# DP_PS.net
KiCad netlist of a schematic drawn in Altium Designer
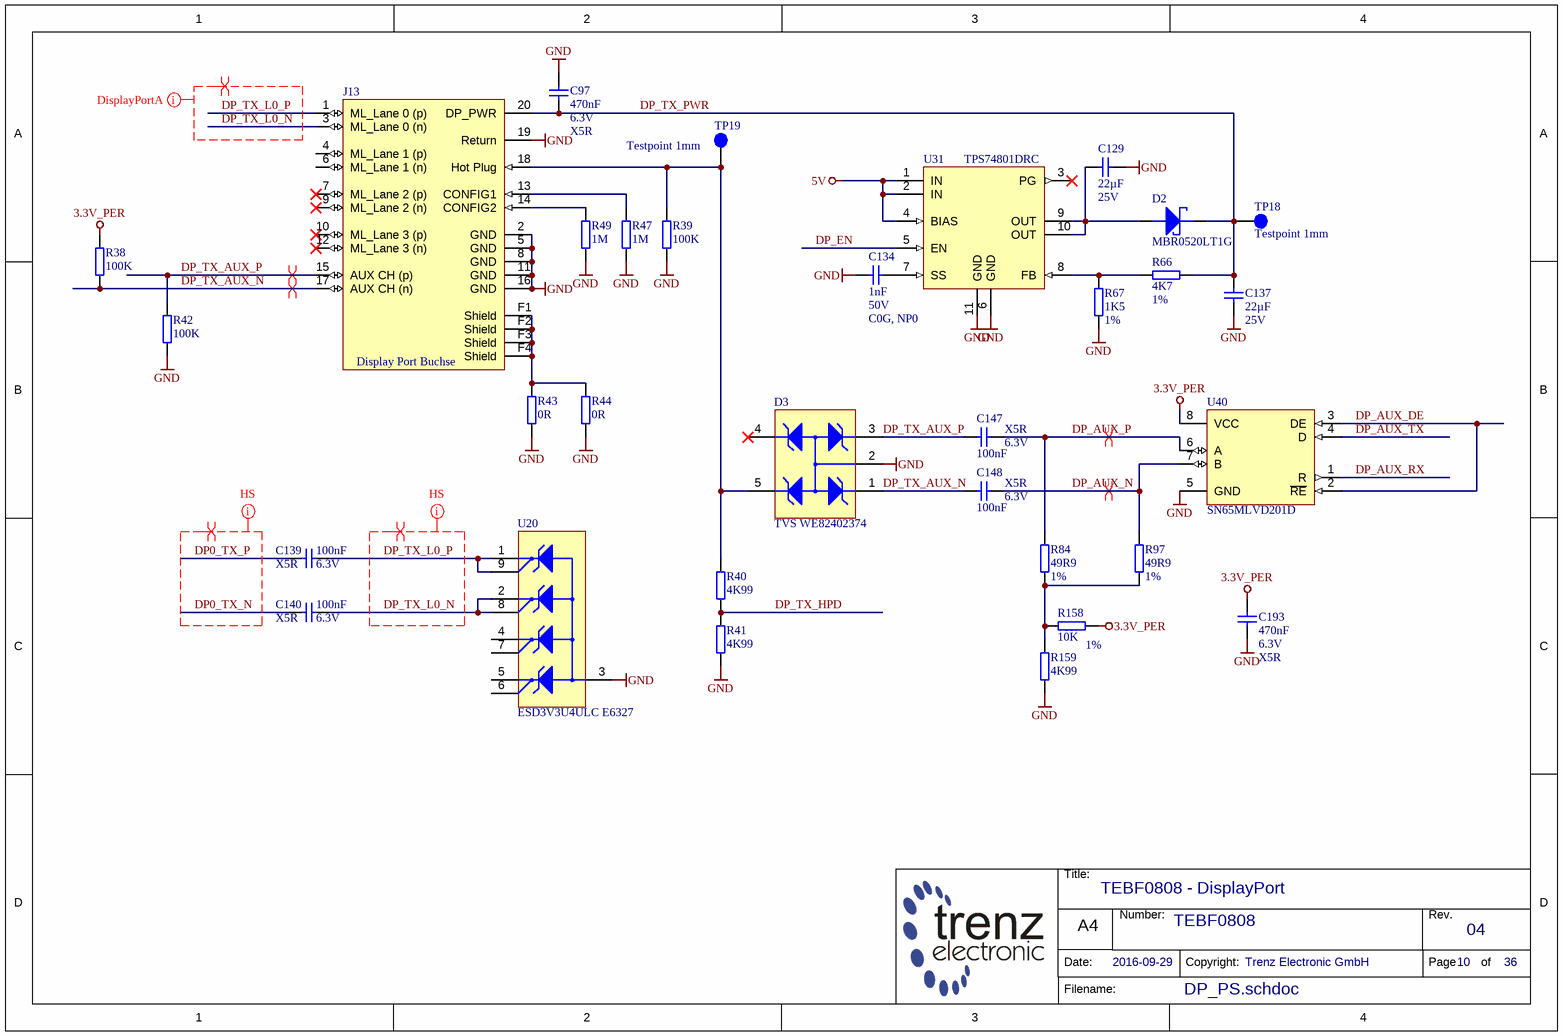
[diagram p0: DP_PS.schdoc]

(export (version "E")
  (design (tool "Eeschema 10.0.6"))
  (components
    (comp (ref "C97")
      (value "470nF")
      (footprint "CAPC1005X55N")
      (description "KON 470nF 6,3V X5R SMD")
      (fields (field (name "VOLTAGE") "6.3V") (field (name "TECHNOLOGY") "X5R"))
      (libsource (lib "TE") (part "CAP-NP"))
    )
    (comp (ref "C129")
      (value "22µF")
      (footprint "CAPC3216X180N")
      (description "KON 22µF X5R 25V SMD 10%")
      (fields (field (name "VOLTAGE") "25V") (field (name "TOLERANCE") "10%"))
      (libsource (lib "TE") (part "CAP-NP"))
    )
    (comp (ref "C134")
      (value "1nF")
      (footprint "CAPC1005X55N")
      (description "KON 1nF NP0 SMD 5%")
      (fields
        (field (name "VOLTAGE") "50V")
        (field (name "TECHNOLOGY") "C0G, NP0")
        (field (name "TOLERANCE") "5%")
      )
      (libsource (lib "TE") (part "CAP-NP"))
    )
    (comp (ref "C137")
      (value "22µF")
      (footprint "CAPC3216X180N")
      (description "KON 22µF X5R 25V SMD 10%")
      (fields (field (name "VOLTAGE") "25V") (field (name "TOLERANCE") "10%"))
      (libsource (lib "TE") (part "CAP-NP"))
    )
    (comp (ref "C139")
      (value "100nF")
      (footprint "CAPC0603X33N")
      (description "KON 100nF 6.3V X5R SMD 10%")
      (fields
        (field (name "VOLTAGE") "6.3V")
        (field (name "TECHNOLOGY") "X5R")
        (field (name "TOLERANCE") "10%")
      )
      (libsource (lib "TE") (part "CAP-NP"))
    )
    (comp (ref "C140")
      (value "100nF")
      (footprint "CAPC0603X33N")
      (description "KON 100nF 6.3V X5R SMD 10%")
      (fields
        (field (name "VOLTAGE") "6.3V")
        (field (name "TECHNOLOGY") "X5R")
        (field (name "TOLERANCE") "10%")
      )
      (libsource (lib "TE") (part "CAP-NP"))
    )
    (comp (ref "C147")
      (value "100nF")
      (footprint "CAPC0603X33N")
      (description "KON 100nF 6.3V X5R SMD 10%")
      (fields
        (field (name "VOLTAGE") "6.3V")
        (field (name "TECHNOLOGY") "X5R")
        (field (name "TOLERANCE") "10%")
      )
      (libsource (lib "TE") (part "CAP-NP"))
    )
    (comp (ref "C148")
      (value "100nF")
      (footprint "CAPC0603X33N")
      (description "KON 100nF 6.3V X5R SMD 10%")
      (fields
        (field (name "VOLTAGE") "6.3V")
        (field (name "TECHNOLOGY") "X5R")
        (field (name "TOLERANCE") "10%")
      )
      (libsource (lib "TE") (part "CAP-NP"))
    )
    (comp (ref "C193")
      (value "470nF")
      (footprint "CAPC1005X55N")
      (description "KON 470nF 6,3V X5R SMD")
      (fields (field (name "VOLTAGE") "6.3V") (field (name "TECHNOLOGY") "X5R"))
      (libsource (lib "TE") (part "CAP-NP"))
    )
    (comp (ref "D2")
      (value "MBR0520LT1G")
      (footprint "SOD3816X120N")
      (fields (field (name "VOLTAGE") "0.5A"))
      (libsource (lib "TE") (part "SCHOTTKY"))
    )
    (comp (ref "D3")
      (value "TVS WE82402374")
      (footprint "SOT65P210X110-5N")
      (description "WE-TVS Array 82402374")
      (libsource (lib "TE") (part "WE-TVS-82402374"))
    )
    (comp (ref "J13")
      (value "Display Port Buchse")
      (footprint "8470-2-2-X")
      (description "DisplayPort Verbinder, Buchse liegend")
      (libsource (lib "TE") (part "DisplayPort"))
    )
    (comp (ref "R38")
      (value "100K")
      (footprint "RESC1005X40N")
      (description "WID SMD 100K 1% 0,063W")
      (fields (field (name "TOLERANCE") "1%"))
      (libsource (lib "TE") (part "RES"))
    )
    (comp (ref "R39")
      (value "100K")
      (footprint "RESC1005X40N")
      (description "WID SMD 100K 1% 0,063W")
      (fields (field (name "TOLERANCE") "1%"))
      (libsource (lib "TE") (part "RES"))
    )
    (comp (ref "R40")
      (value "4K99")
      (footprint "RESC1005X40N")
      (description "WID SMD 4K99 1% 0,063W")
      (fields (field (name "TOLERANCE") "1%"))
      (libsource (lib "TE") (part "RES"))
    )
    (comp (ref "R41")
      (value "4K99")
      (footprint "RESC1005X40N")
      (description "WID SMD 4K99 1% 0,063W")
      (fields (field (name "TOLERANCE") "1%"))
      (libsource (lib "TE") (part "RES"))
    )
    (comp (ref "R42")
      (value "100K")
      (footprint "RESC1005X40N")
      (description "WID SMD 100K 1% 0,063W")
      (fields (field (name "TOLERANCE") "1%"))
      (libsource (lib "TE") (part "RES"))
    )
    (comp (ref "R43")
      (value "0R")
      (footprint "RESC1005X40N")
      (description "WID SMD 0R")
      (fields (field (name "TOLERANCE") "1%"))
      (libsource (lib "TE") (part "RES"))
    )
    (comp (ref "R44")
      (value "0R")
      (footprint "RESC1005X40N")
      (description "WID SMD 0R")
      (fields (field (name "TOLERANCE") "1%"))
      (libsource (lib "TE") (part "RES"))
    )
    (comp (ref "R47")
      (value "1M")
      (footprint "RESC1005X40N")
      (description "WID SMD 1M 1% 0,063W")
      (fields (field (name "TOLERANCE") "1%"))
      (libsource (lib "TE") (part "RES"))
    )
    (comp (ref "R49")
      (value "1M")
      (footprint "RESC1005X40N")
      (description "WID SMD 1M 1% 0,063W")
      (fields (field (name "TOLERANCE") "1%"))
      (libsource (lib "TE") (part "RES"))
    )
    (comp (ref "R66")
      (value "4K7")
      (footprint "RESC1005X40N")
      (description "WID SMD 4K7 1% 0,063W")
      (fields (field (name "TOLERANCE") "1%"))
      (libsource (lib "TE") (part "RES"))
    )
    (comp (ref "R67")
      (value "1K5")
      (footprint "RESC1005X40N")
      (description "WID SMD 1K5 1% 0,063W")
      (fields (field (name "TOLERANCE") "1%"))
      (libsource (lib "TE") (part "RES"))
    )
    (comp (ref "R84")
      (value "49R9")
      (footprint "RESC1005X40N")
      (description "WID SMD 49R9 1% 0,063W")
      (fields (field (name "TOLERANCE") "1%"))
      (libsource (lib "TE") (part "RES"))
    )
    (comp (ref "R97")
      (value "49R9")
      (footprint "RESC1005X40N")
      (description "WID SMD 49R9 1% 0,063W")
      (fields (field (name "TOLERANCE") "1%"))
      (libsource (lib "TE") (part "RES"))
    )
    (comp (ref "R158")
      (value "10K")
      (footprint "RESC1005X40N")
      (description "WID SMD 10K 1% 0,063W")
      (fields (field (name "TOLERANCE") "1%"))
      (libsource (lib "TE") (part "RES"))
    )
    (comp (ref "R159")
      (value "4K99")
      (footprint "RESC1005X40N")
      (description "WID SMD 4K99 1% 0,063W")
      (fields (field (name "TOLERANCE") "1%"))
      (libsource (lib "TE") (part "RES"))
    )
    (comp (ref "TP18") (value "Testpoint 1mm") (footprint "TP_1mm") (libsource (lib "TE") (part "TP")))
    (comp (ref "TP19") (value "Testpoint 1mm") (footprint "TP_1mm") (libsource (lib "TE") (part "TP")))
    (comp (ref "U20")
      (value "ESD3V3U4ULC E6327")
      (footprint "TSLP-9-1")
      (description "TVS UL Cap. 4xIOs ESD 3.3V")
      (libsource (lib "TE") (part "ESD3V3U4ULC"))
    )
    (comp (ref "U31")
      (value "TPS74801DRC")
      (footprint "SON50P300X300X100-11N-TI")
      (libsource (lib "TE") (part "TPS74801DRC"))
    )
    (comp (ref "U40")
      (value "SN65MLVD201D")
      (footprint "SOIC127P600X175-8N")
      (libsource (lib "TE") (part "SN65MLVD201D"))
    )
  )
  (nets
    (net (code "1") (name "/DP0_TX_N") (class "Default")
      (node (ref "C140") (pin "1") (pinfunction "1_1") (pintype "passive"))
    )
    (net (code "2") (name "/DP0_TX_P") (class "Default")
      (node (ref "C139") (pin "1") (pinfunction "1_1") (pintype "passive"))
    )
    (net (code "3") (name "/DP_AUX_DE") (class "Default")
      (node (ref "U40") (pin "2") (pinfunction "~{RE}_2") (pintype "input"))
      (node (ref "U40") (pin "3") (pinfunction "DE_3") (pintype "input"))
    )
    (net (code "4") (name "/DP_AUX_N") (class "Default")
      (node (ref "C148") (pin "2") (pinfunction "2_2") (pintype "passive"))
      (node (ref "R97") (pin "1") (pinfunction "1_1") (pintype "passive"))
      (node (ref "U40") (pin "7") (pinfunction "B_7") (pintype "bidirectional"))
    )
    (net (code "5") (name "/DP_AUX_P") (class "Default")
      (node (ref "C147") (pin "2") (pinfunction "2_2") (pintype "passive"))
      (node (ref "R84") (pin "1") (pinfunction "1_1") (pintype "passive"))
      (node (ref "U40") (pin "6") (pinfunction "A_6") (pintype "bidirectional"))
    )
    (net (code "6") (name "/DP_AUX_RX") (class "Default")
      (node (ref "U40") (pin "1") (pinfunction "R_1") (pintype "output"))
    )
    (net (code "7") (name "/DP_AUX_TX") (class "Default")
      (node (ref "U40") (pin "4") (pinfunction "D_4") (pintype "input"))
    )
    (net (code "8") (name "/DP_EN") (class "Default")
      (node (ref "U31") (pin "5") (pinfunction "EN_5") (pintype "input"))
    )
    (net (code "9") (name "/DP_TX_AUX_N") (class "Default")
      (node (ref "C148") (pin "1") (pinfunction "1_1") (pintype "passive"))
      (node (ref "D3") (pin "1") (pintype "passive"))
      (node (ref "J13") (pin "17") (pinfunction "AUX CH (n)_17") (pintype "bidirectional"))
      (node (ref "R38") (pin "2") (pinfunction "2_2") (pintype "passive"))
    )
    (net (code "10") (name "/DP_TX_AUX_P") (class "Default")
      (node (ref "C147") (pin "1") (pinfunction "1_1") (pintype "passive"))
      (node (ref "D3") (pin "3") (pintype "passive"))
      (node (ref "J13") (pin "15") (pinfunction "AUX CH (p)_15") (pintype "bidirectional"))
      (node (ref "R42") (pin "1") (pinfunction "1_1") (pintype "passive"))
    )
    (net (code "11") (name "/DP_TX_HPD") (class "Default")
      (node (ref "R40") (pin "1") (pinfunction "1_1") (pintype "passive"))
      (node (ref "R41") (pin "2") (pinfunction "2_2") (pintype "passive"))
    )
    (net (code "12") (name "/DP_TX_L0_N") (class "Default")
      (node (ref "C140") (pin "2") (pinfunction "2_2") (pintype "passive"))
      (node (ref "J13") (pin "3") (pinfunction "ML_Lane 0 (n)_3") (pintype "bidirectional"))
      (node (ref "U20") (pin "2") (pinfunction "2_2") (pintype "passive"))
      (node (ref "U20") (pin "8") (pinfunction "8_8") (pintype "passive"))
    )
    (net (code "13") (name "/DP_TX_L0_P") (class "Default")
      (node (ref "C139") (pin "2") (pinfunction "2_2") (pintype "passive"))
      (node (ref "J13") (pin "1") (pinfunction "ML_Lane 0 (p)_1") (pintype "bidirectional"))
      (node (ref "U20") (pin "1") (pinfunction "1_1") (pintype "passive"))
      (node (ref "U20") (pin "9") (pinfunction "9_9") (pintype "passive"))
    )
    (net (code "14") (name "/DP_TX_PWR") (class "Default")
      (node (ref "C137") (pin "2") (pinfunction "2_2") (pintype "passive"))
      (node (ref "C97") (pin "1") (pinfunction "1_1") (pintype "passive"))
      (node (ref "D2") (pin "1") (pinfunction "KATHODE_1") (pintype "passive"))
      (node (ref "J13") (pin "20") (pinfunction "DP_PWR_20") (pintype "power_in"))
      (node (ref "R66") (pin "2") (pinfunction "2_2") (pintype "passive"))
      (node (ref "TP18") (pin "1") (pintype "passive"))
    )
    (net (code "15") (name "3.3V_PER") (class "Default")
      (node (ref "C193") (pin "1") (pinfunction "1_1") (pintype "passive"))
      (node (ref "R158") (pin "1") (pinfunction "1_1") (pintype "passive"))
      (node (ref "R38") (pin "1") (pinfunction "1_1") (pintype "passive"))
      (node (ref "U40") (pin "8") (pinfunction "VCC_8") (pintype "power_in"))
    )
    (net (code "16") (name "5V") (class "Default")
      (node (ref "U31") (pin "1") (pinfunction "IN_1") (pintype "power_in"))
      (node (ref "U31") (pin "2") (pinfunction "IN_2") (pintype "power_in"))
      (node (ref "U31") (pin "4") (pinfunction "BIAS_4") (pintype "input"))
    )
    (net (code "17") (name "GND") (class "Default")
      (node (ref "C129") (pin "2") (pinfunction "2_2") (pintype "passive"))
      (node (ref "C134") (pin "1") (pinfunction "1_1") (pintype "passive"))
      (node (ref "C137") (pin "1") (pinfunction "1_1") (pintype "passive"))
      (node (ref "C193") (pin "2") (pinfunction "2_2") (pintype "passive"))
      (node (ref "C97") (pin "2") (pinfunction "2_2") (pintype "passive"))
      (node (ref "D3") (pin "2") (pintype "passive"))
      (node (ref "J13") (pin "11") (pinfunction "GND_11") (pintype "power_in"))
      (node (ref "J13") (pin "16") (pinfunction "GND_16") (pintype "power_in"))
      (node (ref "J13") (pin "19") (pinfunction "Return_19") (pintype "power_in"))
      (node (ref "J13") (pin "2") (pinfunction "GND_2") (pintype "power_in"))
      (node (ref "J13") (pin "5") (pinfunction "GND_5") (pintype "power_in"))
      (node (ref "J13") (pin "8") (pinfunction "GND_8") (pintype "power_in"))
      (node (ref "R159") (pin "1") (pinfunction "1_1") (pintype "passive"))
      (node (ref "R39") (pin "2") (pinfunction "2_2") (pintype "passive"))
      (node (ref "R41") (pin "1") (pinfunction "1_1") (pintype "passive"))
      (node (ref "R42") (pin "2") (pinfunction "2_2") (pintype "passive"))
      (node (ref "R43") (pin "1") (pinfunction "1_1") (pintype "passive"))
      (node (ref "R44") (pin "1") (pinfunction "1_1") (pintype "passive"))
      (node (ref "R47") (pin "1") (pinfunction "1_1") (pintype "passive"))
      (node (ref "R49") (pin "2") (pinfunction "2_2") (pintype "passive"))
      (node (ref "R67") (pin "2") (pinfunction "2_2") (pintype "passive"))
      (node (ref "U20") (pin "3") (pinfunction "3_3") (pintype "passive"))
      (node (ref "U31") (pin "11") (pinfunction "GND_11") (pintype "power_in"))
      (node (ref "U31") (pin "6") (pinfunction "GND_6") (pintype "power_in"))
      (node (ref "U40") (pin "5") (pinfunction "GND_5") (pintype "power_in"))
    )
    (net (code "18") (name "Net-(D2-ANODE)") (class "Default")
      (node (ref "C129") (pin "1") (pinfunction "1_1") (pintype "passive"))
      (node (ref "D2") (pin "2") (pinfunction "ANODE_2") (pintype "passive"))
      (node (ref "U31") (pin "10") (pinfunction "OUT_10") (pintype "power_in"))
      (node (ref "U31") (pin "9") (pinfunction "OUT_9") (pintype "power_in"))
    )
    (net (code "19") (name "Net-(J13-CONFIG1)") (class "Default")
      (node (ref "J13") (pin "13") (pinfunction "CONFIG1_13") (pintype "input"))
      (node (ref "R47") (pin "2") (pinfunction "2_2") (pintype "passive"))
    )
    (net (code "20") (name "Net-(J13-CONFIG2)") (class "Default")
      (node (ref "J13") (pin "14") (pinfunction "CONFIG2_14") (pintype "input"))
      (node (ref "R49") (pin "1") (pinfunction "1_1") (pintype "passive"))
    )
    (net (code "21") (name "Net-(J13-Hot Plug)") (class "Default")
      (node (ref "D3") (pin "5") (pintype "passive"))
      (node (ref "J13") (pin "18") (pinfunction "Hot Plug_18") (pintype "input"))
      (node (ref "R39") (pin "1") (pinfunction "1_1") (pintype "passive"))
      (node (ref "R40") (pin "2") (pinfunction "2_2") (pintype "passive"))
      (node (ref "TP19") (pin "1") (pintype "passive"))
    )
    (net (code "22") (name "Net-(J13-Shield-PadF1)") (class "Default")
      (node (ref "J13") (pin "F1") (pinfunction "Shield_F1") (pintype "passive"))
      (node (ref "J13") (pin "F2") (pinfunction "Shield_F2") (pintype "passive"))
      (node (ref "J13") (pin "F3") (pinfunction "Shield_F3") (pintype "passive"))
      (node (ref "J13") (pin "F4") (pinfunction "Shield_F4") (pintype "passive"))
      (node (ref "R43") (pin "2") (pinfunction "2_2") (pintype "passive"))
      (node (ref "R44") (pin "2") (pinfunction "2_2") (pintype "passive"))
    )
    (net (code "23") (name "Net-(R158-Pad2)") (class "Default")
      (node (ref "R158") (pin "2") (pinfunction "2_2") (pintype "passive"))
      (node (ref "R159") (pin "2") (pinfunction "2_2") (pintype "passive"))
      (node (ref "R84") (pin "2") (pinfunction "2_2") (pintype "passive"))
      (node (ref "R97") (pin "2") (pinfunction "2_2") (pintype "passive"))
    )
    (net (code "24") (name "Net-(U31-FB)") (class "Default")
      (node (ref "R66") (pin "1") (pinfunction "1_1") (pintype "passive"))
      (node (ref "R67") (pin "1") (pinfunction "1_1") (pintype "passive"))
      (node (ref "U31") (pin "8") (pinfunction "FB_8") (pintype "input"))
    )
    (net (code "25") (name "Net-(U31-SS)") (class "Default")
      (node (ref "C134") (pin "2") (pinfunction "2_2") (pintype "passive"))
      (node (ref "U31") (pin "7") (pinfunction "SS_7") (pintype "input"))
    )
    (net (code "26") (name "unconnected-(D3-Pad4)") (class "Default")
      (node (ref "D3") (pin "4") (pintype "passive+no_connect"))
    )
    (net (code "27") (name "unconnected-(J13-ML_Lane 1 (n)-Pad6)") (class "Default")
      (node (ref "J13") (pin "6") (pinfunction "ML_Lane 1 (n)_6") (pintype "bidirectional"))
    )
    (net (code "28") (name "unconnected-(J13-ML_Lane 1 (p)-Pad4)") (class "Default")
      (node (ref "J13") (pin "4") (pinfunction "ML_Lane 1 (p)_4") (pintype "bidirectional"))
    )
    (net (code "29") (name "unconnected-(J13-ML_Lane 2 (n)-Pad9)") (class "Default")
      (node (ref "J13") (pin "9") (pinfunction "ML_Lane 2 (n)_9") (pintype "bidirectional+no_connect"))
    )
    (net (code "30") (name "unconnected-(J13-ML_Lane 2 (p)-Pad7)") (class "Default")
      (node (ref "J13") (pin "7") (pinfunction "ML_Lane 2 (p)_7") (pintype "bidirectional+no_connect"))
    )
    (net (code "31") (name "unconnected-(J13-ML_Lane 3 (n)-Pad12)") (class "Default")
      (node (ref "J13") (pin "12") (pinfunction "ML_Lane 3 (n)_12") (pintype "bidirectional+no_connect"))
    )
    (net (code "32") (name "unconnected-(J13-ML_Lane 3 (p)-Pad10)") (class "Default")
      (node (ref "J13") (pin "10") (pinfunction "ML_Lane 3 (p)_10") (pintype "bidirectional+no_connect"))
    )
    (net (code "33") (name "unconnected-(U20-Pad4)") (class "Default")
      (node (ref "U20") (pin "4") (pinfunction "4_4") (pintype "passive"))
    )
    (net (code "34") (name "unconnected-(U20-Pad5)") (class "Default")
      (node (ref "U20") (pin "5") (pinfunction "5_5") (pintype "passive"))
    )
    (net (code "35") (name "unconnected-(U20-Pad6)") (class "Default")
      (node (ref "U20") (pin "6") (pinfunction "6_6") (pintype "passive"))
    )
    (net (code "36") (name "unconnected-(U20-Pad7)") (class "Default")
      (node (ref "U20") (pin "7") (pinfunction "7_7") (pintype "passive"))
    )
    (net (code "37") (name "unconnected-(U31-PG-Pad3)") (class "Default")
      (node (ref "U31") (pin "3") (pinfunction "PG_3") (pintype "output+no_connect"))
    )
  )
)
